# LED_Array.net
KiCad netlist of a schematic drawn in EAGLE
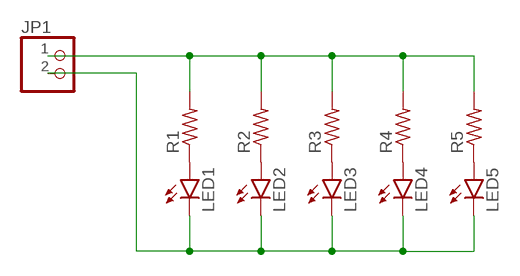
[diagram p0: schematic, sheet 1]

(export (version "E")
  (design (tool "Eeschema 10.0.6"))
  (components
    (comp (ref "JP1")
      (value "PINHD-1X2")
      (footprint "eagle-import:1X02")
      (libsource (lib "eagle-import") (part "PINHD-1X2"))
    )
    (comp (ref "LED1")
      (value "LED3MM")
      (footprint "eagle-import:LED3MM")
      (libsource (lib "eagle-import") (part "LED3MM"))
    )
    (comp (ref "LED2")
      (value "LED3MM")
      (footprint "eagle-import:LED3MM")
      (libsource (lib "eagle-import") (part "LED3MM"))
    )
    (comp (ref "LED3")
      (value "LED3MM")
      (footprint "eagle-import:LED3MM")
      (libsource (lib "eagle-import") (part "LED3MM"))
    )
    (comp (ref "LED4")
      (value "LED3MM")
      (footprint "eagle-import:LED3MM")
      (libsource (lib "eagle-import") (part "LED3MM"))
    )
    (comp (ref "LED5")
      (value "LED3MM")
      (footprint "eagle-import:LED3MM")
      (libsource (lib "eagle-import") (part "LED3MM"))
    )
    (comp (ref "R1")
      (value "R-US_0207/12")
      (footprint "eagle-import:0207_12")
      (libsource (lib "eagle-import") (part "R-US_0207/12"))
    )
    (comp (ref "R2")
      (value "R-US_0207/12")
      (footprint "eagle-import:0207_12")
      (libsource (lib "eagle-import") (part "R-US_0207/12"))
    )
    (comp (ref "R3")
      (value "R-US_0207/12")
      (footprint "eagle-import:0207_12")
      (libsource (lib "eagle-import") (part "R-US_0207/12"))
    )
    (comp (ref "R4")
      (value "R-US_0207/12")
      (footprint "eagle-import:0207_12")
      (libsource (lib "eagle-import") (part "R-US_0207/12"))
    )
    (comp (ref "R5")
      (value "R-US_0207/12")
      (footprint "eagle-import:0207_12")
      (libsource (lib "eagle-import") (part "R-US_0207/12"))
    )
  )
  (nets
    (net (code "1") (name "Net-(JP1-Pad1)") (class "Default")
      (node (ref "JP1") (pin "1") (pinfunction "1_1") (pintype "passive"))
      (node (ref "R1") (pin "2") (pinfunction "2_2") (pintype "passive"))
      (node (ref "R2") (pin "2") (pinfunction "2_2") (pintype "passive"))
      (node (ref "R3") (pin "2") (pinfunction "2_2") (pintype "passive"))
      (node (ref "R4") (pin "2") (pinfunction "2_2") (pintype "passive"))
      (node (ref "R5") (pin "2") (pinfunction "2_2") (pintype "passive"))
    )
    (net (code "2") (name "Net-(LED1-C)") (class "Default")
      (node (ref "JP1") (pin "2") (pinfunction "2_2") (pintype "passive"))
      (node (ref "LED1") (pin "K") (pinfunction "C_K") (pintype "passive"))
      (node (ref "LED2") (pin "K") (pinfunction "C_K") (pintype "passive"))
      (node (ref "LED3") (pin "K") (pinfunction "C_K") (pintype "passive"))
      (node (ref "LED4") (pin "K") (pinfunction "C_K") (pintype "passive"))
      (node (ref "LED5") (pin "K") (pinfunction "C_K") (pintype "passive"))
    )
    (net (code "3") (name "Net-(LED1-PadA)") (class "Default")
      (node (ref "LED1") (pin "A") (pinfunction "A_A") (pintype "passive"))
      (node (ref "R1") (pin "1") (pinfunction "1_1") (pintype "passive"))
    )
    (net (code "4") (name "Net-(LED2-PadA)") (class "Default")
      (node (ref "LED2") (pin "A") (pinfunction "A_A") (pintype "passive"))
      (node (ref "R2") (pin "1") (pinfunction "1_1") (pintype "passive"))
    )
    (net (code "5") (name "Net-(LED3-PadA)") (class "Default")
      (node (ref "LED3") (pin "A") (pinfunction "A_A") (pintype "passive"))
      (node (ref "R3") (pin "1") (pinfunction "1_1") (pintype "passive"))
    )
    (net (code "6") (name "Net-(LED4-PadA)") (class "Default")
      (node (ref "LED4") (pin "A") (pinfunction "A_A") (pintype "passive"))
      (node (ref "R4") (pin "1") (pinfunction "1_1") (pintype "passive"))
    )
    (net (code "7") (name "Net-(LED5-PadA)") (class "Default")
      (node (ref "LED5") (pin "A") (pinfunction "A_A") (pintype "passive"))
      (node (ref "R5") (pin "1") (pinfunction "1_1") (pintype "passive"))
    )
  )
)
